# Welduino.net
KiCad netlist of a schematic drawn in EAGLE
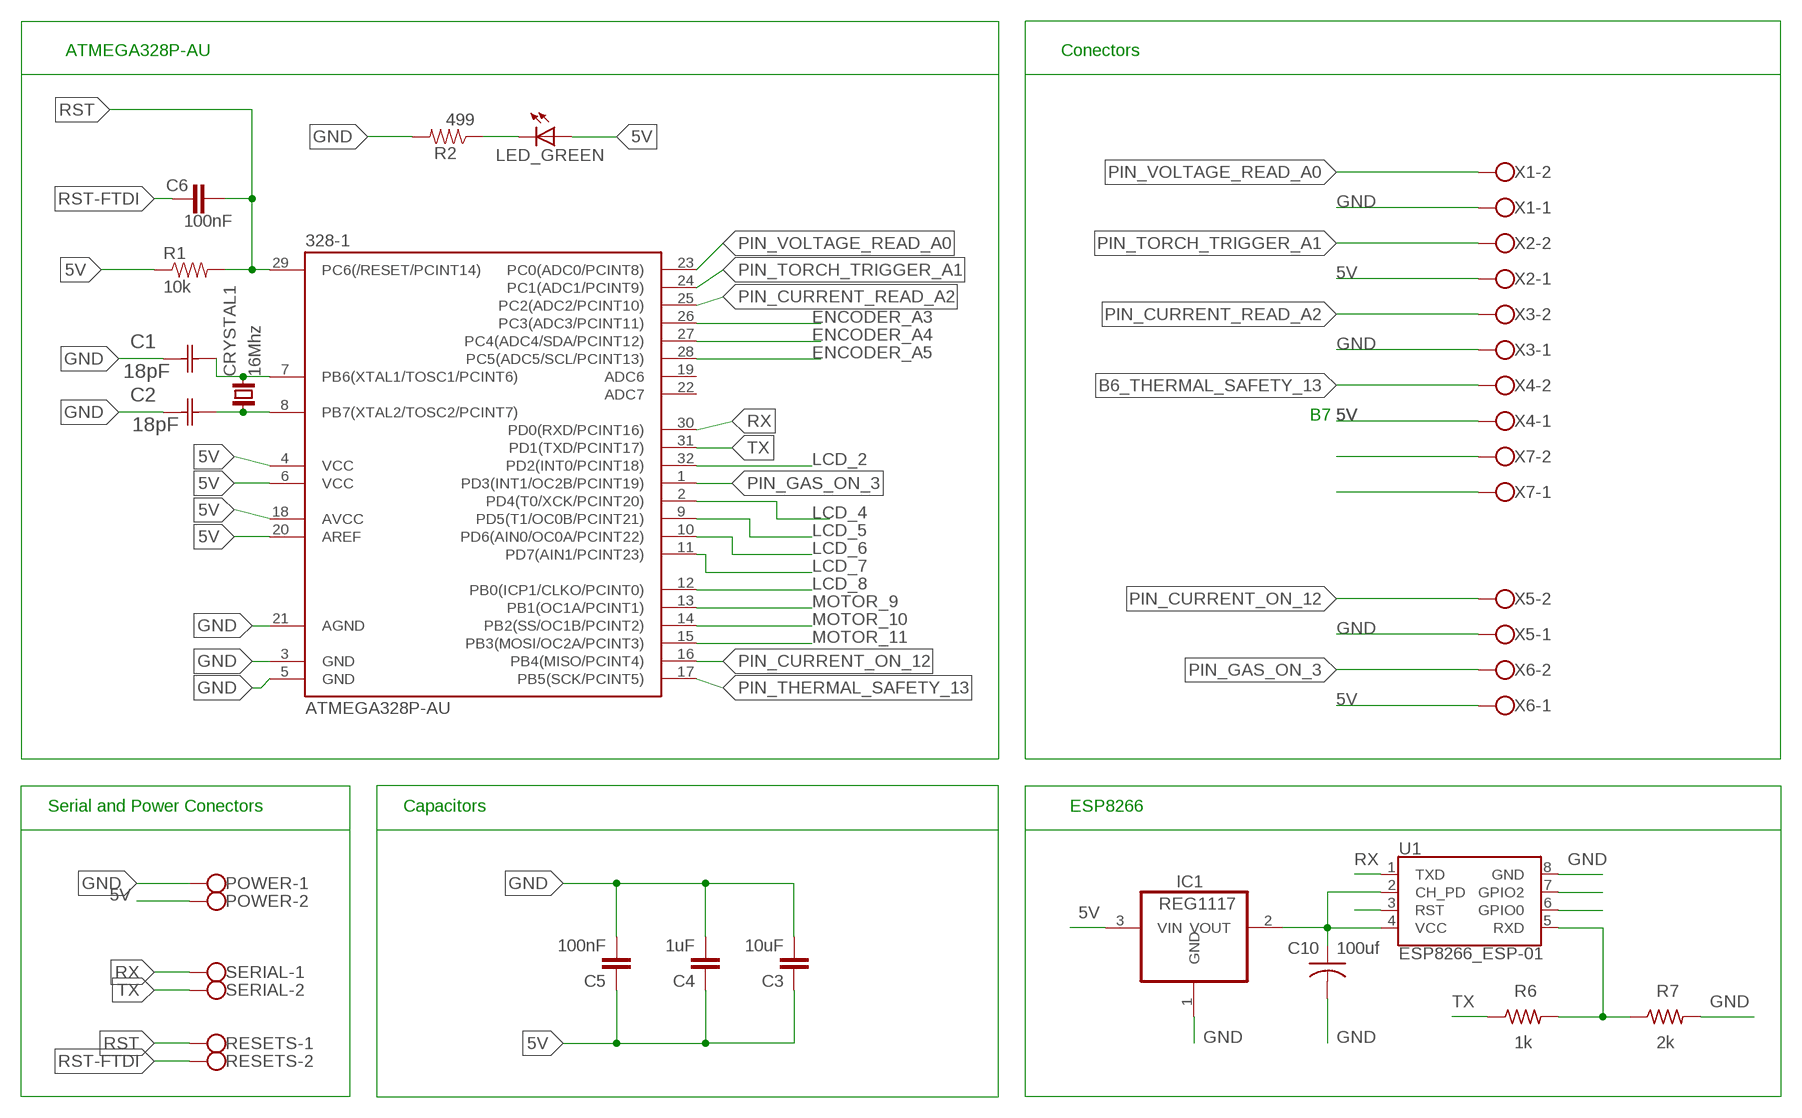
[diagram p0: schematic, sheet 1]

(export (version "E")
  (design (tool "Eeschema 10.0.6"))
  (components
    (comp (ref "328-1")
      (value "ATMEGA328P-AU")
      (footprint "eagle-import:TQFP32-08")
      (libsource (lib "eagle-import") (part "ATMEGA48/88/168-AU"))
    )
    (comp (ref "C1")
      (value "18pF")
      (footprint "eagle-import:CAPC3216X178N")
      (fields (field (name "MPN") "0612ZC225MAT2A") (field (name "TOLERANCE") "±20%"))
      (libsource (lib "eagle-import") (part "0612ZC225MAT2A"))
    )
    (comp (ref "C2")
      (value "18pF")
      (footprint "eagle-import:CAPC3216X178N")
      (fields (field (name "MPN") "0612ZC225MAT2A") (field (name "TOLERANCE") "±20%"))
      (libsource (lib "eagle-import") (part "0612ZC225MAT2A"))
    )
    (comp (ref "C3")
      (value "10uF")
      (footprint "eagle-import:1206")
      (libsource (lib "eagle-import") (part "CAP1206"))
    )
    (comp (ref "C4")
      (value "1uF")
      (footprint "eagle-import:1206")
      (libsource (lib "eagle-import") (part "CAP1206"))
    )
    (comp (ref "C5")
      (value "100nF")
      (footprint "eagle-import:1206")
      (libsource (lib "eagle-import") (part "CAP1206"))
    )
    (comp (ref "C6")
      (value "100nF")
      (footprint "eagle-import:1206")
      (libsource (lib "eagle-import") (part "CAP1206"))
    )
    (comp (ref "C10")
      (value "100uf")
      (footprint "eagle-import:C1206FAB")
      (libsource (lib "eagle-import") (part "CAP-US1206FAB"))
    )
    (comp (ref "CRYSTAL1")
      (value "16Mhz")
      (footprint "eagle-import:2-SMD-5X3")
      (fields (field (name "MF") "NDK America,") (field (name "MP") "NX5032GA"))
      (libsource (lib "eagle-import") (part "NX5032GA"))
    )
    (comp (ref "IC1")
      (value "REG1117")
      (footprint "eagle-import:SOT223")
      (libsource (lib "eagle-import") (part "REG1117"))
    )
    (comp (ref "LED_GREEN")
      (value "LED1206")
      (footprint "eagle-import:1206")
      (libsource (lib "eagle-import") (part "LED1206"))
    )
    (comp (ref "POWER")
      (value "W237-102")
      (footprint "eagle-import:W237-102")
      (fields (field (name "MPN") "237-102"))
      (libsource (lib "eagle-import") (part "W237-102"))
    )
    (comp (ref "R1")
      (value "10k")
      (footprint "eagle-import:1206")
      (libsource (lib "eagle-import") (part "RESISTOR1206"))
    )
    (comp (ref "R2")
      (value "499")
      (footprint "eagle-import:1206")
      (libsource (lib "eagle-import") (part "RESISTOR1206"))
    )
    (comp (ref "R6")
      (value "1k")
      (footprint "eagle-import:R1206FAB")
      (libsource (lib "eagle-import") (part "RES-US1206FAB"))
    )
    (comp (ref "R7")
      (value "2k")
      (footprint "eagle-import:R1206FAB")
      (libsource (lib "eagle-import") (part "RES-US1206FAB"))
    )
    (comp (ref "RESETS")
      (value "W237-102")
      (footprint "eagle-import:W237-102")
      (fields (field (name "MPN") "237-102"))
      (libsource (lib "eagle-import") (part "W237-102"))
    )
    (comp (ref "SERIAL")
      (value "W237-102")
      (footprint "eagle-import:W237-102")
      (fields (field (name "MPN") "237-102"))
      (libsource (lib "eagle-import") (part "W237-102"))
    )
    (comp (ref "U1")
      (value "ESP8266_ESP-01")
      (footprint "eagle-import:ESP8266_ESP-01")
      (libsource (lib "eagle-import") (part "ESP8266_ESP-01"))
    )
    (comp (ref "X1")
      (value "W237-102")
      (footprint "eagle-import:W237-102")
      (fields (field (name "MPN") "237-102"))
      (libsource (lib "eagle-import") (part "W237-102"))
    )
    (comp (ref "X2")
      (value "W237-102")
      (footprint "eagle-import:W237-102")
      (fields (field (name "MPN") "237-102"))
      (libsource (lib "eagle-import") (part "W237-102"))
    )
    (comp (ref "X3")
      (value "W237-102")
      (footprint "eagle-import:W237-102")
      (fields (field (name "MPN") "237-102"))
      (libsource (lib "eagle-import") (part "W237-102"))
    )
    (comp (ref "X4")
      (value "W237-102")
      (footprint "eagle-import:W237-102")
      (fields (field (name "MPN") "237-102"))
      (libsource (lib "eagle-import") (part "W237-102"))
    )
    (comp (ref "X5")
      (value "W237-102")
      (footprint "eagle-import:W237-102")
      (fields (field (name "MPN") "237-102"))
      (libsource (lib "eagle-import") (part "W237-102"))
    )
    (comp (ref "X6")
      (value "W237-102")
      (footprint "eagle-import:W237-102")
      (fields (field (name "MPN") "237-102"))
      (libsource (lib "eagle-import") (part "W237-102"))
    )
    (comp (ref "X7")
      (value "W237-102")
      (footprint "eagle-import:W237-102")
      (fields (field (name "MPN") "237-102"))
      (libsource (lib "eagle-import") (part "W237-102"))
    )
  )
  (nets
    (net (code "1") (name "5V") (class "Default")
      (node (ref "328-1") (pin "18") (pinfunction "AVCC_18") (pintype "passive"))
      (node (ref "328-1") (pin "20") (pinfunction "AREF_20") (pintype "passive"))
      (node (ref "328-1") (pin "4") (pinfunction "VCC_4") (pintype "power_in"))
      (node (ref "328-1") (pin "6") (pinfunction "VCC_6") (pintype "power_in"))
      (node (ref "C3") (pin "1") (pinfunction "1_1") (pintype "passive"))
      (node (ref "C4") (pin "1") (pinfunction "1_1") (pintype "passive"))
      (node (ref "C5") (pin "1") (pinfunction "1_1") (pintype "passive"))
      (node (ref "IC1") (pin "3") (pinfunction "VIN_3") (pintype "input"))
      (node (ref "LED_GREEN") (pin "1") (pinfunction "A_1") (pintype "passive"))
      (node (ref "POWER") (pin "2") (pinfunction "KL_2") (pintype "passive"))
      (node (ref "R1") (pin "1") (pinfunction "1_1") (pintype "passive"))
      (node (ref "X2") (pin "1") (pinfunction "KL_1") (pintype "passive"))
      (node (ref "X4") (pin "1") (pinfunction "KL_1") (pintype "passive"))
      (node (ref "X6") (pin "1") (pinfunction "KL_1") (pintype "passive"))
    )
    (net (code "2") (name "B6_THERMAL_SAFETY_13") (class "Default")
      (node (ref "X4") (pin "2") (pinfunction "KL_2") (pintype "passive"))
    )
    (net (code "3") (name "ENCODER_A3") (class "Default")
      (node (ref "328-1") (pin "26") (pinfunction "PC3(ADC3/PCINT11)_26") (pintype "bidirectional"))
    )
    (net (code "4") (name "ENCODER_A4") (class "Default")
      (node (ref "328-1") (pin "27") (pinfunction "PC4(ADC4/SDA/PCINT12)_27") (pintype "bidirectional"))
    )
    (net (code "5") (name "ENCODER_A5") (class "Default")
      (node (ref "328-1") (pin "28") (pinfunction "PC5(ADC5/SCL/PCINT13)_28") (pintype "bidirectional"))
    )
    (net (code "6") (name "GND") (class "Default")
      (node (ref "328-1") (pin "21") (pinfunction "AGND_21") (pintype "power_in"))
      (node (ref "328-1") (pin "3") (pinfunction "GND_3") (pintype "power_in"))
      (node (ref "328-1") (pin "5") (pinfunction "GND_5") (pintype "power_in"))
      (node (ref "C1") (pin "1") (pinfunction "C1_1") (pintype "passive"))
      (node (ref "C10") (pin "2") (pinfunction "2_2") (pintype "passive"))
      (node (ref "C2") (pin "1") (pinfunction "C1_1") (pintype "passive"))
      (node (ref "C3") (pin "2") (pinfunction "2_2") (pintype "passive"))
      (node (ref "C4") (pin "2") (pinfunction "2_2") (pintype "passive"))
      (node (ref "C5") (pin "2") (pinfunction "2_2") (pintype "passive"))
      (node (ref "IC1") (pin "1") (pinfunction "GND_1") (pintype "power_in"))
      (node (ref "POWER") (pin "1") (pinfunction "KL_1") (pintype "passive"))
      (node (ref "R2") (pin "2") (pinfunction "2_2") (pintype "passive"))
      (node (ref "R7") (pin "2") (pinfunction "2_2") (pintype "passive"))
      (node (ref "U1") (pin "8") (pinfunction "GND_8") (pintype "bidirectional"))
      (node (ref "X1") (pin "1") (pinfunction "KL_1") (pintype "passive"))
      (node (ref "X3") (pin "1") (pinfunction "KL_1") (pintype "passive"))
      (node (ref "X5") (pin "1") (pinfunction "KL_1") (pintype "passive"))
    )
    (net (code "7") (name "LCD_2") (class "Default")
      (node (ref "328-1") (pin "32") (pinfunction "PD2(INT0/PCINT18)_32") (pintype "bidirectional"))
    )
    (net (code "8") (name "LCD_4") (class "Default")
      (node (ref "328-1") (pin "2") (pinfunction "PD4(T0/XCK/PCINT20)_2") (pintype "bidirectional"))
    )
    (net (code "9") (name "LCD_5") (class "Default")
      (node (ref "328-1") (pin "9") (pinfunction "PD5(T1/OC0B/PCINT21)_9") (pintype "bidirectional"))
    )
    (net (code "10") (name "LCD_6") (class "Default")
      (node (ref "328-1") (pin "10") (pinfunction "PD6(AIN0/OC0A/PCINT22)_10") (pintype "bidirectional"))
    )
    (net (code "11") (name "LCD_7") (class "Default")
      (node (ref "328-1") (pin "11") (pinfunction "PD7(AIN1/PCINT23)_11") (pintype "bidirectional"))
    )
    (net (code "12") (name "LCD_8") (class "Default")
      (node (ref "328-1") (pin "12") (pinfunction "PB0(ICP1/CLKO/PCINT0)_12") (pintype "bidirectional"))
    )
    (net (code "13") (name "MOTOR_9") (class "Default")
      (node (ref "328-1") (pin "13") (pinfunction "PB1(OC1A/PCINT1)_13") (pintype "bidirectional"))
    )
    (net (code "14") (name "MOTOR_10") (class "Default")
      (node (ref "328-1") (pin "14") (pinfunction "PB2(SS/OC1B/PCINT2)_14") (pintype "bidirectional"))
    )
    (net (code "15") (name "MOTOR_11") (class "Default")
      (node (ref "328-1") (pin "15") (pinfunction "PB3(MOSI/OC2A/PCINT3)_15") (pintype "bidirectional"))
    )
    (net (code "16") (name "Net-(328-1-PB6(XTAL1{slash}TOSC1{slash}PCINT6))") (class "Default")
      (node (ref "328-1") (pin "7") (pinfunction "PB6(XTAL1/TOSC1/PCINT6)_7") (pintype "bidirectional"))
      (node (ref "C1") (pin "2") (pinfunction "C2_2") (pintype "passive"))
      (node (ref "CRYSTAL1") (pin "2") (pinfunction "2_2") (pintype "passive"))
    )
    (net (code "17") (name "Net-(328-1-PB7(XTAL2{slash}TOSC2{slash}PCINT7))") (class "Default")
      (node (ref "328-1") (pin "8") (pinfunction "PB7(XTAL2/TOSC2/PCINT7)_8") (pintype "bidirectional"))
      (node (ref "C2") (pin "2") (pinfunction "C2_2") (pintype "passive"))
      (node (ref "CRYSTAL1") (pin "1") (pinfunction "1_1") (pintype "passive"))
    )
    (net (code "18") (name "Net-(IC1-VOUT)") (class "Default")
      (node (ref "C10") (pin "1") (pinfunction "1_1") (pintype "passive"))
      (node (ref "IC1") (pin "2") (pinfunction "VOUT_2") (pintype "output"))
      (node (ref "U1") (pin "2") (pinfunction "CH_PD_2") (pintype "bidirectional"))
      (node (ref "U1") (pin "4") (pinfunction "VCC_4") (pintype "bidirectional"))
    )
    (net (code "19") (name "Net-(LED_GREEN-C)") (class "Default")
      (node (ref "LED_GREEN") (pin "2") (pinfunction "C_2") (pintype "passive"))
      (node (ref "R2") (pin "1") (pinfunction "1_1") (pintype "passive"))
    )
    (net (code "20") (name "Net-(U1-RXD)") (class "Default")
      (node (ref "R6") (pin "2") (pinfunction "2_2") (pintype "passive"))
      (node (ref "R7") (pin "1") (pinfunction "1_1") (pintype "passive"))
      (node (ref "U1") (pin "5") (pinfunction "RXD_5") (pintype "bidirectional"))
    )
    (net (code "21") (name "PIN_CURRENT_ON_12") (class "Default")
      (node (ref "328-1") (pin "16") (pinfunction "PB4(MISO/PCINT4)_16") (pintype "bidirectional"))
      (node (ref "X5") (pin "2") (pinfunction "KL_2") (pintype "passive"))
    )
    (net (code "22") (name "PIN_CURRENT_READ_A2") (class "Default")
      (node (ref "328-1") (pin "25") (pinfunction "PC2(ADC2/PCINT10)_25") (pintype "bidirectional"))
      (node (ref "X3") (pin "2") (pinfunction "KL_2") (pintype "passive"))
    )
    (net (code "23") (name "PIN_GAS_ON_3") (class "Default")
      (node (ref "328-1") (pin "1") (pinfunction "PD3(INT1/OC2B/PCINT19)_1") (pintype "bidirectional"))
      (node (ref "X6") (pin "2") (pinfunction "KL_2") (pintype "passive"))
    )
    (net (code "24") (name "PIN_THERMAL_SAFETY_13") (class "Default")
      (node (ref "328-1") (pin "17") (pinfunction "PB5(SCK/PCINT5)_17") (pintype "bidirectional"))
    )
    (net (code "25") (name "PIN_TORCH_TRIGGER_A1") (class "Default")
      (node (ref "328-1") (pin "24") (pinfunction "PC1(ADC1/PCINT9)_24") (pintype "bidirectional"))
      (node (ref "X2") (pin "2") (pinfunction "KL_2") (pintype "passive"))
    )
    (net (code "26") (name "PIN_VOLTAGE_READ_A0") (class "Default")
      (node (ref "328-1") (pin "23") (pinfunction "PC0(ADC0/PCINT8)_23") (pintype "bidirectional"))
      (node (ref "X1") (pin "2") (pinfunction "KL_2") (pintype "passive"))
    )
    (net (code "27") (name "RST") (class "Default")
      (node (ref "328-1") (pin "29") (pinfunction "PC6(/RESET/PCINT14)_29") (pintype "bidirectional"))
      (node (ref "C6") (pin "1") (pinfunction "1_1") (pintype "passive"))
      (node (ref "R1") (pin "2") (pinfunction "2_2") (pintype "passive"))
      (node (ref "RESETS") (pin "1") (pinfunction "KL_1") (pintype "passive"))
    )
    (net (code "28") (name "RST-FTDI") (class "Default")
      (node (ref "C6") (pin "2") (pinfunction "2_2") (pintype "passive"))
      (node (ref "RESETS") (pin "2") (pinfunction "KL_2") (pintype "passive"))
    )
    (net (code "29") (name "RX") (class "Default")
      (node (ref "328-1") (pin "30") (pinfunction "PD0(RXD/PCINT16)_30") (pintype "bidirectional"))
      (node (ref "SERIAL") (pin "1") (pinfunction "KL_1") (pintype "passive"))
      (node (ref "U1") (pin "1") (pinfunction "TXD_1") (pintype "bidirectional"))
    )
    (net (code "30") (name "TX") (class "Default")
      (node (ref "328-1") (pin "31") (pinfunction "PD1(TXD/PCINT17)_31") (pintype "bidirectional"))
      (node (ref "R6") (pin "1") (pinfunction "1_1") (pintype "passive"))
      (node (ref "SERIAL") (pin "2") (pinfunction "KL_2") (pintype "passive"))
    )
    (net (code "31") (name "unconnected-(328-1-ADC6-Pad19)") (class "Default")
      (node (ref "328-1") (pin "19") (pinfunction "ADC6_19") (pintype "passive"))
    )
    (net (code "32") (name "unconnected-(328-1-ADC7-Pad22)") (class "Default")
      (node (ref "328-1") (pin "22") (pinfunction "ADC7_22") (pintype "passive"))
    )
    (net (code "33") (name "unconnected-(U1-GPIO0-Pad6)") (class "Default")
      (node (ref "U1") (pin "6") (pinfunction "GPIO0_6") (pintype "bidirectional"))
    )
    (net (code "34") (name "unconnected-(U1-GPIO2-Pad7)") (class "Default")
      (node (ref "U1") (pin "7") (pinfunction "GPIO2_7") (pintype "bidirectional"))
    )
    (net (code "35") (name "unconnected-(U1-RST-Pad3)") (class "Default")
      (node (ref "U1") (pin "3") (pinfunction "RST_3") (pintype "bidirectional"))
    )
    (net (code "36") (name "unconnected-(X7A-KL-Pad1)") (class "Default")
      (node (ref "X7") (pin "1") (pinfunction "KL_1") (pintype "passive"))
    )
    (net (code "37") (name "unconnected-(X7B-KL-Pad2)") (class "Default")
      (node (ref "X7") (pin "2") (pinfunction "KL_2") (pintype "passive"))
    )
  )
)
